# Power_supply.net
KiCad netlist of a schematic drawn in Altium Designer
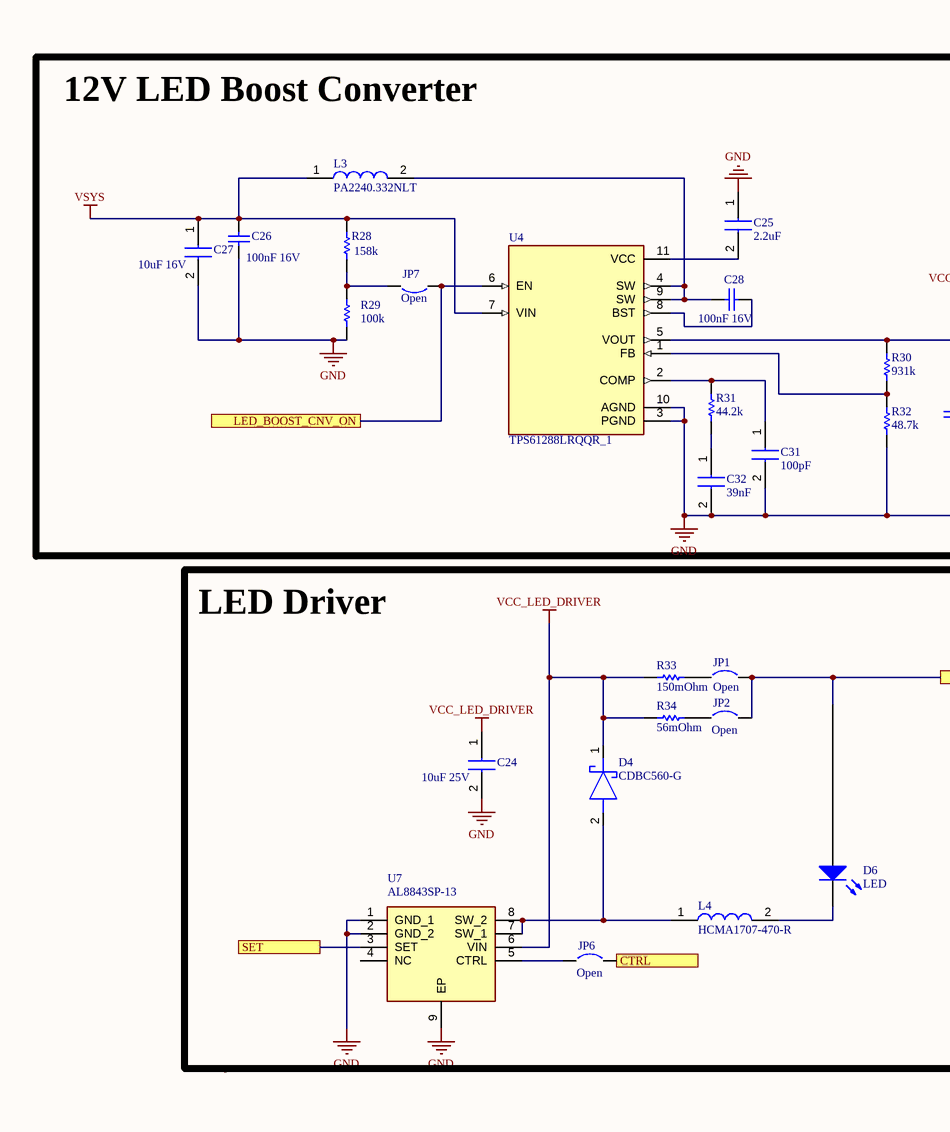
[diagram p0: Power supply.SchDoc, left]
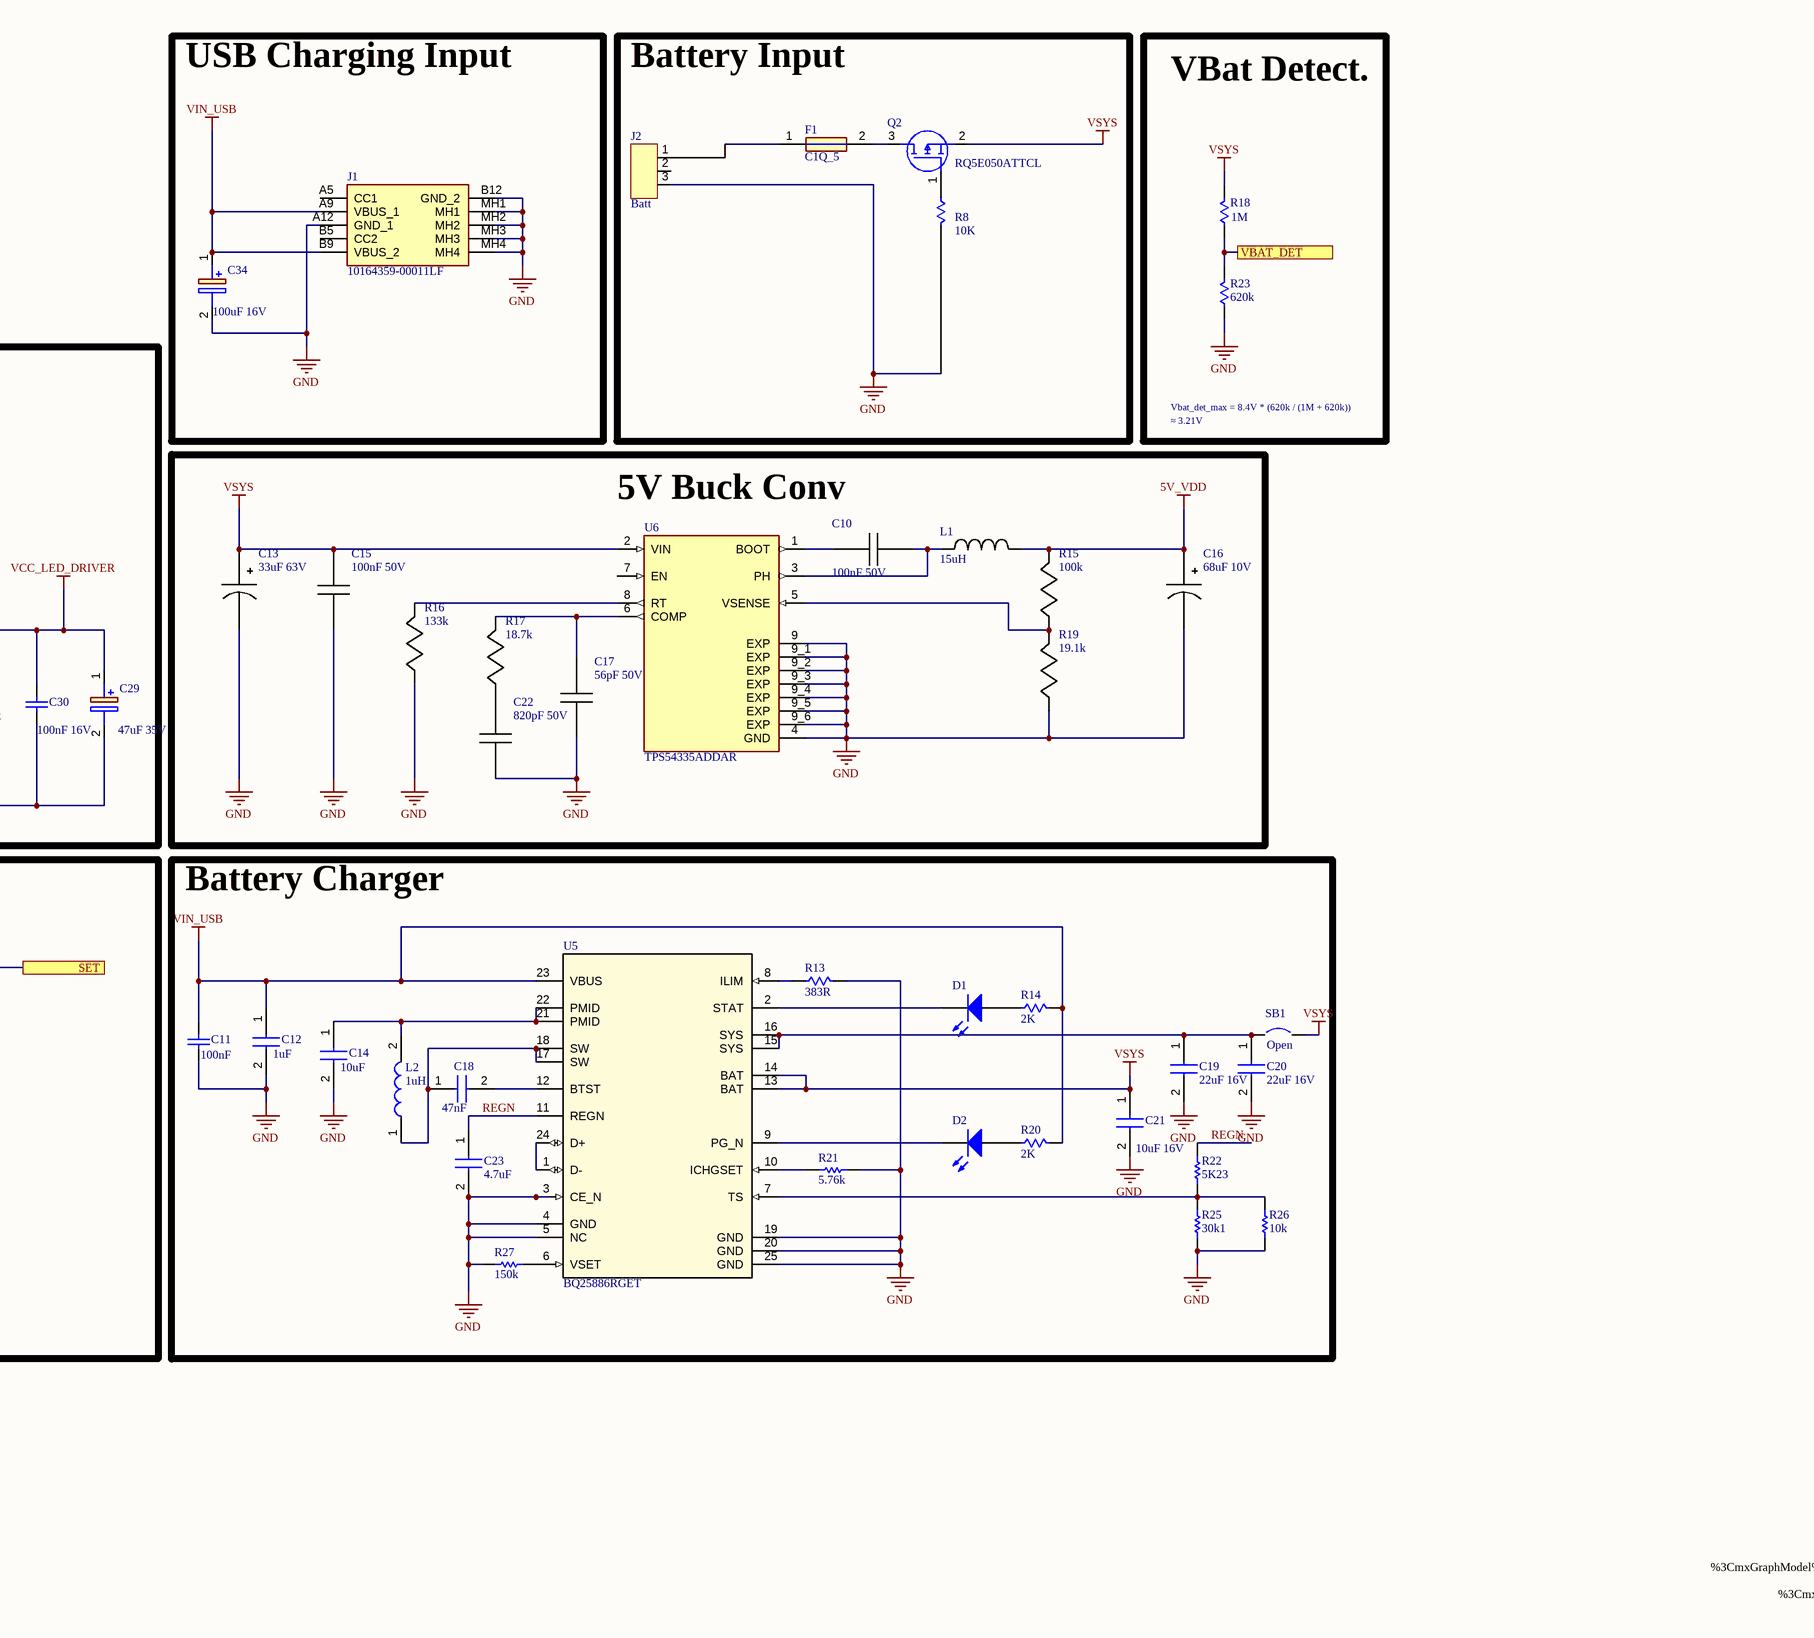
[diagram p1: Power supply.SchDoc, right]

(export (version "E")
  (design (tool "Eeschema 10.0.6"))
  (components
    (comp (ref "C10")
      (value "100nF 50V")
      (footprint "0805C")
      (fields
        (field (name "MANUFACTURER PART NUMBER") "C0805C104M5RACTU")
        (field (name "COPYRIGHT") "Copyright (C) 2018 Accelerated Designs. All rights reserved")
      )
      (libsource (lib "Schlib1") (part "C0805C104M5RACTU"))
    )
    (comp (ref "C11")
      (value "100nF")
      (footprint "C0603")
      (description "CAP CER 0.1UF 16V X7R 0603")
      (fields
        (field (name "MANUFACTURER") "Yageo")
        (field (name "MANUFACTURER PART NUMBER") "CC0603KRX7R7BB104")
      )
      (libsource (lib "Sunbull_V1R0") (part "CC0603KRX7R7BB104"))
    )
    (comp (ref "C12")
      (value "1uF")
      (footprint "PcbLib1:C0805")
      (description "CAP CER 1UF 16V X7R 0805")
      (fields
        (field (name "MOUSER PART NUMBER") "187-CL21B105KOFNNNE")
        (field (name "ARROW PART NUMBER") "CL21B105KOFNNNE")
      )
      (libsource (lib "Sunbull_V1R0") (part "CL21B105KOFNNNE"))
    )
    (comp (ref "C13")
      (value "33uF 63V")
      (footprint "SM_RADIAL_8MM")
      (description "No Description Available")
      (fields
        (field (name "MANUFACTURER PART NUMBER") "EEHZA1J330P")
        (field (name "COPYRIGHT") "Copyright (C) 2018 Accelerated Designs. All rights reserved")
      )
      (libsource (lib "Schlib1") (part "EEHZA1J330P"))
    )
    (comp (ref "C14")
      (value "10uF")
      (footprint "C0603")
      (fields (field (name "MANUFACTURER PART NUMBER") "CL10X106MO8NRNC"))
      (libsource (lib "Sunbull_V1R0") (part "CL21B105KOFNNNE"))
    )
    (comp (ref "C15")
      (value "100nF 50V")
      (footprint "0805C")
      (fields
        (field (name "MANUFACTURER PART NUMBER") "C0805C104M5RACTU")
        (field (name "COPYRIGHT") "Copyright (C) 2018 Accelerated Designs. All rights reserved")
      )
      (libsource (lib "Schlib1") (part "C0805C104M5RACTU"))
    )
    (comp (ref "C16")
      (value "68uF 10V")
      (footprint "SM_RADIAL_5MM")
      (description "10SVPC68M 68uF 10V")
      (fields
        (field (name "MANUFACTURER PART NUMBER") "10SVPC68M")
        (field (name "COPYRIGHT") "Copyright (C) 2018 Accelerated Designs. All rights reserved")
      )
      (libsource (lib "Schlib1") (part "10SVPC68M"))
    )
    (comp (ref "C17")
      (value "56pF 50V")
      (footprint "0805C")
      (fields
        (field (name "MANUFACTURER PART NUMBER") "CC0805JRNPO9BN560")
        (field (name "COPYRIGHT") "Copyright (C) 2018 Accelerated Designs. All rights reserved")
      )
      (libsource (lib "Schlib1") (part "CC0805JRNPO9BN56"))
    )
    (comp (ref "C18")
      (value "47nF")
      (footprint "C0805")
      (fields (field (name "MANUFACTURER PART NUMBER") "KGM21NR71C473KT"))
      (libsource (lib "Sunbull_V1R0") (part "CL21B105KOFNNNE"))
    )
    (comp (ref "C19")
      (value "22uF 16V")
      (footprint "C0603")
      (fields (field (name "MANUFACTURER PART NUMBER") "CL10X106MO8NRNC"))
      (libsource (lib "Sunbull_V1R0") (part "CL21B105KOFNNNE"))
    )
    (comp (ref "C20")
      (value "22uF 16V")
      (footprint "C0603")
      (fields (field (name "MANUFACTURER PART NUMBER") "CL10X106MO8NRNC"))
      (libsource (lib "Sunbull_V1R0") (part "CL21B105KOFNNNE"))
    )
    (comp (ref "C21")
      (value "10uF 16V")
      (footprint "C0603")
      (fields (field (name "MANUFACTURER PART NUMBER") "CL10X106MO8NRNC"))
      (libsource (lib "Sunbull_V1R0") (part "CL21B105KOFNNNE"))
    )
    (comp (ref "C22")
      (value "820pF 50V")
      (footprint "0402")
      (fields
        (field (name "MANUFACTURER PART NUMBER") "CL05C821JB5NNNC")
        (field (name "COPYRIGHT") "Copyright (C) 2018 Accelerated Designs. All rights reserved")
      )
      (libsource (lib "Schlib1") (part "CL05C821JB5NNNC"))
    )
    (comp (ref "C23")
      (value "4.7uF")
      (footprint "C0805")
      (fields (field (name "MANUFACTURER PART NUMBER") "C0805C475M3PAC"))
      (libsource (lib "Sunbull_V1R0") (part "CL21B105KOFNNNE"))
    )
    (comp (ref "C24")
      (value "10uF 25V")
      (footprint "0805C")
      (fields (field (name "MANUFACTURER PART NUMBER") "GRM21BR61E106KA3L"))
      (libsource (lib "Sunbull_V1R0") (part "CL21B105KOFNNNE"))
    )
    (comp (ref "C25")
      (value "2.2uF")
      (footprint "PcbLib1:0805C")
      (fields (field (name "MANUFACTURER PART NUMBER") "CL21B105KOFNNNE"))
      (libsource (lib "Sunbull_V1R0") (part "CL21B105KOFNNNE"))
    )
    (comp (ref "C26")
      (value "100nF 16V")
      (footprint "C0603")
      (description "CAP CER 0.1UF 16V X7R 0603")
      (fields
        (field (name "MANUFACTURER") "Yageo")
        (field (name "MANUFACTURER PART NUMBER") "CC0603KRX7R7BB104")
      )
      (libsource (lib "Sunbull_V1R0") (part "CC0603KRX7R7BB104"))
    )
    (comp (ref "C27")
      (value "10uF 16V")
      (footprint "C0603")
      (fields (field (name "MANUFACTURER PART NUMBER") "CL10X106MO8NRNC"))
      (libsource (lib "Sunbull_V1R0") (part "CL21B105KOFNNNE"))
    )
    (comp (ref "C28")
      (value "100nF 16V")
      (footprint "C0603")
      (description "CAP CER 0.1UF 16V X7R 0603")
      (fields
        (field (name "MANUFACTURER") "Yageo")
        (field (name "MANUFACTURER PART NUMBER") "CC0603KRX7R7BB104")
      )
      (libsource (lib "Sunbull_V1R0") (part "CC0603KRX7R7BB104"))
    )
    (comp (ref "C29")
      (value "47uF 35V")
      (footprint "PcbLib1:CAPAE660X550N")
      (description "Capacitor Polarised")
      (fields
        (field (name "MANUFACTURER PART NUMBER") "865080543009")
        (field (name "MOUSER PART NUMBER") "710-865080543009")
      )
      (libsource (lib "*") (part "865080543009"))
    )
    (comp (ref "C30")
      (value "100nF 16V")
      (footprint "C0603")
      (description "CAP CER 0.1UF 16V X7R 0603")
      (fields
        (field (name "MANUFACTURER") "Yageo")
        (field (name "MANUFACTURER PART NUMBER") "CC0603KRX7R7BB104")
      )
      (libsource (lib "Sunbull_V1R0") (part "CC0603KRX7R7BB104"))
    )
    (comp (ref "C31")
      (value "100pF")
      (footprint "C0603")
      (description "CAP CER 100pF 16V")
      (fields (field (name "MANUFACTURER PART NUMBER") "CC603JRNPO9BN101"))
      (libsource (lib "Sunbull_V1R0") (part "CL21B105KOFNNNE"))
    )
    (comp (ref "C32")
      (value "39nF")
      (footprint "PcbLib1:C0603")
      (description "39nF CAP 0603")
      (fields (field (name "MANUFACTURER PART NUMBER") "06035C393KAT2A"))
      (libsource (lib "Sunbull_V1R0") (part "CL21B105KOFNNNE"))
    )
    (comp (ref "C34")
      (value "100uF 16V")
      (footprint "PcbLib1:CAPAE660X770N")
      (description "Capacitor Polarised")
      (fields
        (field (name "MANUFACTURER PART NUMBER") "865230345005")
        (field (name "MOUSER PART NUMBER") "710-865230345005")
      )
      (libsource (lib "*") (part "865230345005"))
    )
    (comp (ref "D1")
      (value "LED3")
      (footprint "PcbLib1:C0603")
      (description "Typical BLUE SiC LED")
      (fields
        (field (name "MANUFACTURER PART NUMBER") "LTST-C191TBKT")
        (field (name "PUBLISHER") "Altium Limited")
      )
      (libsource (lib "Sunbull_V1R0") (part "LED3"))
    )
    (comp (ref "D2")
      (value "LED3")
      (footprint "PcbLib1:C0603")
      (description "Typical BLUE SiC LED")
      (fields
        (field (name "MANUFACTURER PART NUMBER") "LTST-C191TBKT")
        (field (name "PUBLISHER") "Altium Limited")
      )
      (libsource (lib "Sunbull_V1R0") (part "LED3"))
    )
    (comp (ref "D4")
      (value "CDBC560-G")
      (footprint "PcbLib1:DIOM7959X262N")
      (description "Schottky Diode")
      (fields (field (name "MOUSER PART NUMBER") "750-CDBC560-G"))
      (libsource (lib "*") (part "CDBC560-G"))
    )
    (comp (ref "D6")
      (value "LED")
      (footprint "PcbLib1:SolderWires")
      (libsource (lib "Schlib1") (part "LED3"))
    )
    (comp (ref "F1")
      (value "C1Q_5")
      (footprint "FUSC3216X78N")
      (description "FUSE BOARD MOUNT 5A 125VAC 63VDC")
      (fields (field (name "MOUSER PART NUMBER") "530-C1Q5") (field (name "ARROW PART NUMBER") "C1Q 5"))
      (libsource (lib "Sunbull_V1R0") (part "C1Q_5"))
    )
    (comp (ref "J1")
      (value "10164359-00011LF")
      (footprint "PcbLib1:1016435900011LF")
      (description "Connector")
      (fields (field (name "MOUSER PART NUMBER") "649-10164359-00011LF"))
      (libsource (lib "*") (part "10164359-00011LF"))
    )
    (comp (ref "J2") (value "Batt") (footprint "Batt") (libsource (lib "Schlib1") (part "Batt")))
    (comp (ref "JP1")
      (value "Open")
      (footprint "HDRV2W87P0X254_1X2_768X249X1494P - duplicate")
      (description "Conn\r\n42375-1855\r\n+\r\njumper\r\n60900213621")
      (fields (field (name "PUBLISHER") "Altium Limited"))
      (libsource (lib "Schlib1") (part "Circuit Breaker_close"))
    )
    (comp (ref "JP2")
      (value "Open")
      (footprint "HDRV2W87P0X254_1X2_768X249X1494P - duplicate")
      (description "Conn\r\n42375-1855\r\n+\r\njumper\r\n60900213621")
      (fields (field (name "PUBLISHER") "Altium Limited"))
      (libsource (lib "Schlib1") (part "Circuit Breaker_close"))
    )
    (comp (ref "JP6")
      (value "Open")
      (footprint "HDRV2W87P0X254_1X2_768X249X1494P - duplicate")
      (description "Jumper\r\n42375-1855")
      (fields (field (name "PUBLISHER") "Altium Limited"))
      (libsource (lib "Schlib1") (part "Circuit Breaker_close"))
    )
    (comp (ref "JP7")
      (value "Open")
      (footprint "HDRV2W87P0X254_1X2_768X249X1494P - duplicate")
      (description "Jumper\r\n42375-1855")
      (fields (field (name "PUBLISHER") "Altium Limited"))
      (libsource (lib "Schlib1") (part "Circuit Breaker_close"))
    )
    (comp (ref "L1")
      (value "15uH")
      (footprint "SRR1280")
      (description "No Description Available")
      (fields
        (field (name "MANUFACTURER PART NUMBER") "SRR1280-150M")
        (field (name "COPYRIGHT") "Copyright (C) 2018 Accelerated Designs. All rights reserved")
      )
      (libsource (lib "Schlib1") (part "SRR1280-150M"))
    )
    (comp (ref "L2")
      (value "1uH")
      (footprint "PcbLib1:VLS5045EX330M")
      (description "Inductor")
      (fields
        (field (name "MANUFACTURER PART NUMBER") "VLS5045EX-1R0N")
        (field (name "MOUSER PART NUMBER") "810-VLS5045EX-1R0N")
      )
      (libsource (lib "Schlib1") (part "VLS5045EX-1R0N"))
    )
    (comp (ref "L3")
      (value "PA2240.332NLT")
      (footprint "PA2240332NLT")
      (description "Inductor")
      (fields (field (name "MOUSER PART NUMBER") "673-PA2240.332NLT"))
      (libsource (lib "Schlib1") (part "PA2240.332NLT"))
    )
    (comp (ref "L4")
      (value "HCMA1707-470-R")
      (footprint "PcbLib1:INDPM172168X700N")
      (description "Inductor")
      (fields (field (name "MOUSER PART NUMBER") "704-HCMA1707-470-R"))
      (libsource (lib "Schlib1") (part "HCMA1707-470-R"))
    )
    (comp (ref "Q2")
      (value "RQ5E050ATTCL")
      (footprint "SOT95P280X100-3N")
      (description "MOSFET P-CH 30V 5A TSMT3")
      (fields (field (name "MOUSER PART NUMBER") "755-RQ5E050ATTCL") (field (name "MANUFACTURER") "Rohm"))
      (libsource (lib "Sunbull_V1R0") (part "RQ5E050ATTCL"))
    )
    (comp (ref "R8")
      (value "10K")
      (footprint "PcbLib1:0603")
      (description "RES SMD 10K OHM 1% 1/10W 0603")
      (fields (field (name "TOLERANCE") "1%") (field (name "MANUFACTURER PART NUMBER") "RC0603FR-0710KL"))
      (libsource (lib "Sunbull_V1R0") (part "RC0603FR-0710KL"))
    )
    (comp (ref "R13")
      (value "383R")
      (footprint "R0603")
      (fields
        (field (name "MANUFACTURER PART NUMBER") "ERJ-3EKF3830V")
        (field (name "TOLERANCE") "±1%")
        (field (name "MOUSER PART NUMBER") "603-RC0603FR-072KL")
      )
      (libsource (lib "Sunbull_V1R0") (part "RC0603FR-072KL"))
    )
    (comp (ref "R14")
      (value "2K")
      (footprint "PcbLib1:R0603")
      (description "RES SMD 2K OHM 1% 1/10W 0603")
      (fields
        (field (name "MANUFACTURER") "Yageo")
        (field (name "MANUFACTURER PART NUMBER") "RC0603FR-072KL")
      )
      (libsource (lib "Sunbull_V1R0") (part "RC0603FR-072KL"))
    )
    (comp (ref "R15")
      (value "100k")
      (footprint "0402")
      (description "100k Resistor")
      (fields
        (field (name "POWER") "0.063")
        (field (name "TOLERANCE") "1.0")
        (field (name "COPYRIGHT") "Copyright (C) 2018 Accelerated Designs. All rights reserved")
      )
      (libsource (lib "Schlib1") (part "CRCW0402100KFKED"))
    )
    (comp (ref "R16")
      (value "133k")
      (footprint "0201")
      (fields
        (field (name "POWER") "0.05")
        (field (name "TOLERANCE") "1.0")
        (field (name "MANUFACTURER PART NUMBER") "RC0201FR-07133KL")
        (field (name "COPYRIGHT") "Copyright (C) 2018 Accelerated Designs. All rights reserved")
      )
      (libsource (lib "Schlib1") (part "RC0201FR-07133KL"))
    )
    (comp (ref "R17")
      (value "18.7k")
      (footprint "0201")
      (fields
        (field (name "POWER") "0.05")
        (field (name "TOLERANCE") "1.0")
        (field (name "MANUFACTURER PART NUMBER") "RC0201FR-0718K7L")
        (field (name "COPYRIGHT") "Copyright (C) 2018 Accelerated Designs. All rights reserved")
      )
      (libsource (lib "Schlib1") (part "RC0201FR-0718K7L"))
    )
    (comp (ref "R18")
      (value "1M")
      (footprint "PcbLib1:0603")
      (description "RES SMD 1M OHM 1% 1/10W 0603")
      (fields (field (name "MANUFACTURER PART NUMBER") "RC0603FR-071ML") (field (name "TOLERANCE") "1%"))
      (libsource (lib "Sunbull_V1R0") (part "RC0603FR-071ML"))
    )
    (comp (ref "R19")
      (value "19.1k")
      (footprint "0402")
      (fields
        (field (name "POWER") "0.063")
        (field (name "TOLERANCE") "1.0")
        (field (name "MANUFACTURER PART NUMBER") "CRCW040219K1FKED")
        (field (name "COPYRIGHT") "Copyright (C) 2018 Accelerated Designs. All rights reserved")
      )
      (libsource (lib "Schlib1") (part "CRCW040219K1FKED"))
    )
    (comp (ref "R20")
      (value "2K")
      (footprint "PcbLib1:R0603")
      (description "RES SMD 2K OHM 1% 1/10W 0603")
      (fields
        (field (name "MANUFACTURER") "Yageo")
        (field (name "MANUFACTURER PART NUMBER") "RC0603FR-072KL")
      )
      (libsource (lib "Sunbull_V1R0") (part "RC0603FR-072KL"))
    )
    (comp (ref "R21")
      (value "5.76k")
      (footprint "R0603")
      (description "Resistor DNP 0603 5.76k")
      (fields (field (name "MANUFACTURER PART NUMBER") "RC0603FR-075K76L"))
      (libsource (lib "Sunbull_V1R0") (part "RES_DNP"))
    )
    (comp (ref "R22")
      (value "5K23")
      (footprint "R0603")
      (description "Resistor DNP 0603")
      (fields (field (name "MANUFACTURER PART NUMBER") "ERJ-3EKF5231V"))
      (libsource (lib "Sunbull_V1R0") (part "RES_DNP"))
    )
    (comp (ref "R23")
      (value "620k")
      (footprint "PcbLib1:0603")
      (description "RES SMD 620k OHM 1% 1/10W 0603")
      (fields (field (name "MANUFACTURER PART NUMBER") "CRCW0603620KFKEA") (field (name "TOLERANCE") "1%"))
      (libsource (lib "Sunbull_V1R0") (part "RC0603FR-071ML"))
    )
    (comp (ref "R25")
      (value "30k1")
      (footprint "PcbLib1:R0603")
      (description "Resistor DNP 0603")
      (fields (field (name "MANUFACTURER PART NUMBER") "CRCW0603-30.1K-E3"))
      (libsource (lib "Sunbull_V1R0") (part "RES_DNP"))
    )
    (comp (ref "R26")
      (value "10k")
      (footprint "PcbLib1:R0603")
      (description "Resistor DNP 0603")
      (fields (field (name "MANUFACTURER PART NUMBER") "CRCW0603-10K-E3"))
      (libsource (lib "Sunbull_V1R0") (part "RES_DNP"))
    )
    (comp (ref "R27")
      (value "150k")
      (footprint "R0603")
      (description "Resistor DNP 0603")
      (fields (field (name "MANUFACTURER PART NUMBER") "RT0603BRE07250RL"))
      (libsource (lib "Sunbull_V1R0") (part "RES_DNP"))
    )
    (comp (ref "R28")
      (value "158k")
      (footprint "PcbLib1:0603")
      (description "Resistor DNP 0603 158k")
      (fields (field (name "MANUFACTURER PART NUMBER") "CRCW0603-158K-E3"))
      (libsource (lib "Sunbull_V1R0") (part "RES_DNP"))
    )
    (comp (ref "R29")
      (value "100k")
      (footprint "R0603")
      (description "RES SMD 100K OHM 1% 1/10W 0603")
      (fields
        (field (name "MANUFACTURER") "Yageo")
        (field (name "MANUFACTURER PART NUMBER") "RC0603FR-07100KL")
      )
      (libsource (lib "Sunbull_V1R0") (part "RC0603FR-07100KL"))
    )
    (comp (ref "R30")
      (value "931k")
      (footprint "PcbLib1:R0603")
      (description "Resistor DNP 0603")
      (fields (field (name "MANUFACTURER PART NUMBER") "CRCW0603-931K-E3"))
      (libsource (lib "Sunbull_V1R0") (part "RES_DNP"))
    )
    (comp (ref "R31")
      (value "44.2k")
      (footprint "PcbLib1:R0603")
      (description "Resistor DNP 0603")
      (fields (field (name "MANUFACTURER PART NUMBER") "CRCW0603-44.2K-E3"))
      (libsource (lib "Sunbull_V1R0") (part "RES_DNP"))
    )
    (comp (ref "R32")
      (value "48.7k")
      (footprint "PcbLib1:R0603")
      (description "Resistor DNP 0603")
      (fields (field (name "MANUFACTURER PART NUMBER") "CRCW0603-48.7K-E3"))
      (libsource (lib "Sunbull_V1R0") (part "RES_DNP"))
    )
    (comp (ref "R33")
      (value "150mOhm")
      (footprint "PcbLib1:R0603")
      (description "Resistor DNP 0603 150mOhm RL0603FR-070R15L")
      (fields (field (name "MANUFACTURER PART NUMBER") "RL0603FR-070R15L"))
      (libsource (lib "Sunbull_V1R0") (part "RES_DNP"))
    )
    (comp (ref "R34")
      (value "56mOhm")
      (footprint "PcbLib1:R0603")
      (description "Resistor DNP 0603 ERJ-3BWFR056V 56mOhm")
      (fields (field (name "MANUFACTURER PART NUMBER") "ERJ-3BWFR056V"))
      (libsource (lib "Sunbull_V1R0") (part "RES_DNP"))
    )
    (comp (ref "SB1")
      (value "Open")
      (footprint "SB_0603")
      (description "Circuit Breaker")
      (fields (field (name "PUBLISHER") "Altium Limited"))
      (libsource (lib "Sunbull_V1R0") (part "Circuit Breaker_close"))
    )
    (comp (ref "U4")
      (value "TPS61288LRQQR_1")
      (footprint "CONV_TPS61288LRQQR")
      (description "18-V, 15-A synchronous boost converter")
      (fields
        (field (name "MF") "Texas Instruments")
        (field (name "MANUFACTURER PART NUMBER") "TPS61288LRQQR")
      )
      (libsource (lib "Schlib1") (part "TPS61288LRQQR_1"))
    )
    (comp (ref "U5")
      (value "BQ25886RGET")
      (footprint "RGE0024H")
      (description "No Description Available")
      (libsource (lib "Schlib1") (part "BQ25886RGET"))
    )
    (comp (ref "U6")
      (value "TPS54335ADDAR")
      (footprint "IC_TPS54335ADDAR")
      (description "4.5V to 28V Input, 3A, Synchronous, Step-Down Converter with Eco-mode")
      (libsource (lib "Schlib1") (part "TPS54335ADDAR"))
    )
    (comp (ref "U7")
      (value "AL8843SP-13")
      (footprint "PcbLib1:SOIC127P600X163-9N")
      (description "Integrated Circuit")
      (fields (field (name "MOUSER PART NUMBER") "621-AL8843SP-13"))
      (libsource (lib "Schlib1") (part "AL8843SP-13"))
    )
  )
  (nets
    (net (code "1") (name "/CTRL") (class "Default")
      (node (ref "JP6") (pin "2") (pinfunction "2_2") (pintype "passive"))
    )
    (net (code "2") (name "/LED_BOOST_CNV_ON") (class "Default")
      (node (ref "JP7") (pin "1") (pinfunction "1_1") (pintype "passive"))
      (node (ref "U4") (pin "6") (pinfunction "EN_6") (pintype "input"))
    )
    (net (code "3") (name "/REGN") (class "Default")
      (node (ref "C23") (pin "1") (pinfunction "1_1") (pintype "passive"))
      (node (ref "R22") (pin "1") (pinfunction "1_1") (pintype "passive"))
      (node (ref "U5") (pin "11") (pinfunction "REGN_11") (pintype "power_in"))
    )
    (net (code "4") (name "/SET") (class "Default")
      (node (ref "D6") (pin "1") (pinfunction "A_1") (pintype "passive"))
      (node (ref "JP1") (pin "2") (pinfunction "2_2") (pintype "passive"))
      (node (ref "JP2") (pin "2") (pinfunction "2_2") (pintype "passive"))
      (node (ref "U7") (pin "3") (pinfunction "SET_3") (pintype "passive"))
    )
    (net (code "5") (name "/VBAT_DET") (class "Default")
      (node (ref "R18") (pin "1") (pinfunction "1_1") (pintype "passive"))
      (node (ref "R23") (pin "2") (pinfunction "2_2") (pintype "passive"))
    )
    (net (code "6") (name "5V_VDD") (class "Default")
      (node (ref "C16") (pin "1") (pinfunction "+_1") (pintype "passive"))
      (node (ref "L1") (pin "2") (pinfunction "2_2") (pintype "passive"))
      (node (ref "R15") (pin "1") (pinfunction "1_1") (pintype "passive"))
    )
    (net (code "7") (name "GND") (class "Default")
      (node (ref "C11") (pin "1") (pinfunction "1_1") (pintype "passive"))
      (node (ref "C12") (pin "2") (pinfunction "2_2") (pintype "passive"))
      (node (ref "C13") (pin "2") (pinfunction "-_2") (pintype "passive"))
      (node (ref "C14") (pin "2") (pinfunction "2_2") (pintype "passive"))
      (node (ref "C15") (pin "1") (pinfunction "1_1") (pintype "passive"))
      (node (ref "C16") (pin "2") (pinfunction "-_2") (pintype "passive"))
      (node (ref "C17") (pin "2") (pinfunction "2_2") (pintype "passive"))
      (node (ref "C19") (pin "2") (pinfunction "2_2") (pintype "passive"))
      (node (ref "C20") (pin "2") (pinfunction "2_2") (pintype "passive"))
      (node (ref "C21") (pin "2") (pinfunction "2_2") (pintype "passive"))
      (node (ref "C22") (pin "2") (pinfunction "2_2") (pintype "passive"))
      (node (ref "C23") (pin "2") (pinfunction "2_2") (pintype "passive"))
      (node (ref "C24") (pin "2") (pinfunction "2_2") (pintype "passive"))
      (node (ref "C25") (pin "1") (pinfunction "1_1") (pintype "passive"))
      (node (ref "C26") (pin "1") (pinfunction "1_1") (pintype "passive"))
      (node (ref "C27") (pin "2") (pinfunction "2_2") (pintype "passive"))
      (node (ref "C29") (pin "2") (pinfunction "-_2") (pintype "passive"))
      (node (ref "C30") (pin "1") (pinfunction "1_1") (pintype "passive"))
      (node (ref "C31") (pin "2") (pinfunction "2_2") (pintype "passive"))
      (node (ref "C32") (pin "2") (pinfunction "2_2") (pintype "passive"))
      (node (ref "C34") (pin "2") (pinfunction "-_2") (pintype "passive"))
      (node (ref "J1") (pin "A12") (pinfunction "GND_1_A12") (pintype "passive"))
      (node (ref "J1") (pin "B12") (pinfunction "GND_2_B12") (pintype "passive"))
      (node (ref "J1") (pin "MH1") (pinfunction "MH1_MH1") (pintype "passive"))
      (node (ref "J1") (pin "MH2") (pinfunction "MH2_MH2") (pintype "passive"))
      (node (ref "J1") (pin "MH3") (pinfunction "MH3_MH3") (pintype "passive"))
      (node (ref "J1") (pin "MH4") (pinfunction "MH4_MH4") (pintype "passive"))
      (node (ref "J2") (pin "3") (pinfunction "3_3") (pintype "passive"))
      (node (ref "R13") (pin "2") (pinfunction "2_2") (pintype "passive"))
      (node (ref "R16") (pin "2") (pinfunction "2_2") (pintype "passive"))
      (node (ref "R19") (pin "2") (pinfunction "2_2") (pintype "passive"))
      (node (ref "R21") (pin "2") (pinfunction "2_2") (pintype "passive"))
      (node (ref "R23") (pin "1") (pinfunction "1_1") (pintype "passive"))
      (node (ref "R25") (pin "2") (pinfunction "2_2") (pintype "passive"))
      (node (ref "R26") (pin "2") (pinfunction "2_2") (pintype "passive"))
      (node (ref "R27") (pin "1") (pinfunction "1_1") (pintype "passive"))
      (node (ref "R29") (pin "1") (pinfunction "1_1") (pintype "passive"))
      (node (ref "R32") (pin "1") (pinfunction "1_1") (pintype "passive"))
      (node (ref "R8") (pin "2") (pinfunction "2_2") (pintype "passive"))
      (node (ref "U4") (pin "10") (pinfunction "AGND_10") (pintype "power_in"))
      (node (ref "U4") (pin "3") (pinfunction "PGND_3") (pintype "power_in"))
      (node (ref "U5") (pin "19") (pinfunction "GND_19") (pintype "power_in"))
      (node (ref "U5") (pin "20") (pinfunction "GND_20") (pintype "power_in"))
      (node (ref "U5") (pin "25") (pinfunction "GND_25") (pintype "power_in"))
      (node (ref "U5") (pin "3") (pinfunction "CE_N_3") (pintype "input"))
      (node (ref "U5") (pin "4") (pinfunction "GND_4") (pintype "power_in"))
      (node (ref "U5") (pin "5") (pinfunction "NC_5") (pintype "passive"))
      (node (ref "U6") (pin "4") (pinfunction "GND_4") (pintype "power_in"))
      (node (ref "U6") (pin "9") (pinfunction "EXP_9") (pintype "power_in"))
      (node (ref "U6") (pin "9_1") (pinfunction "EXP_9_1") (pintype "power_in"))
      (node (ref "U6") (pin "9_2") (pinfunction "EXP_9_2") (pintype "power_in"))
      (node (ref "U6") (pin "9_3") (pinfunction "EXP_9_3") (pintype "power_in"))
      (node (ref "U6") (pin "9_4") (pinfunction "EXP_9_4") (pintype "power_in"))
      (node (ref "U6") (pin "9_5") (pinfunction "EXP_9_5") (pintype "power_in"))
      (node (ref "U6") (pin "9_6") (pinfunction "EXP_9_6") (pintype "power_in"))
      (node (ref "U7") (pin "1") (pinfunction "GND_1_1") (pintype "passive"))
      (node (ref "U7") (pin "2") (pinfunction "GND_2_2") (pintype "passive"))
      (node (ref "U7") (pin "9") (pinfunction "EP_9") (pintype "passive"))
    )
    (net (code "8") (name "Net-(C14-Pad1)") (class "Default")
      (node (ref "C14") (pin "1") (pinfunction "1_1") (pintype "passive"))
      (node (ref "L2") (pin "2") (pinfunction "2_2") (pintype "passive"))
      (node (ref "U5") (pin "21") (pinfunction "PMID_21") (pintype "power_in"))
      (node (ref "U5") (pin "22") (pinfunction "PMID_22") (pintype "power_in"))
    )
    (net (code "9") (name "Net-(C18-Pad1)") (class "Default")
      (node (ref "C18") (pin "1") (pinfunction "1_1") (pintype "passive"))
      (node (ref "L2") (pin "1") (pinfunction "1_1") (pintype "passive"))
      (node (ref "U5") (pin "17") (pinfunction "SW_17") (pintype "power_in"))
      (node (ref "U5") (pin "18") (pinfunction "SW_18") (pintype "power_in"))
    )
    (net (code "10") (name "Net-(C19-Pad1)") (class "Default")
      (node (ref "C19") (pin "1") (pinfunction "1_1") (pintype "passive"))
      (node (ref "C20") (pin "1") (pinfunction "1_1") (pintype "passive"))
      (node (ref "SB1") (pin "1") (pinfunction "1_1") (pintype "passive"))
      (node (ref "U5") (pin "15") (pinfunction "SYS_15") (pintype "power_in"))
      (node (ref "U5") (pin "16") (pinfunction "SYS_16") (pintype "power_in"))
    )
    (net (code "11") (name "Net-(C22-Pad1)") (class "Default")
      (node (ref "C22") (pin "1") (pinfunction "1_1") (pintype "passive"))
      (node (ref "R17") (pin "2") (pinfunction "2_2") (pintype "passive"))
    )
    (net (code "12") (name "Net-(C28-Pad2)") (class "Default")
      (node (ref "C28") (pin "2") (pinfunction "2_2") (pintype "passive"))
      (node (ref "L3") (pin "2") (pinfunction "2_2") (pintype "passive"))
      (node (ref "U4") (pin "4") (pinfunction "SW_4") (pintype "output"))
      (node (ref "U4") (pin "9") (pinfunction "SW_9") (pintype "output"))
    )
    (net (code "13") (name "Net-(C32-Pad1)") (class "Default")
      (node (ref "C32") (pin "1") (pinfunction "1_1") (pintype "passive"))
      (node (ref "R31") (pin "1") (pinfunction "1_1") (pintype "passive"))
    )
    (net (code "14") (name "Net-(D1-A)") (class "Default")
      (node (ref "D1") (pin "1") (pinfunction "A_1") (pintype "passive"))
      (node (ref "R14") (pin "1") (pinfunction "1_1") (pintype "passive"))
    )
    (net (code "15") (name "Net-(D1-K)") (class "Default")
      (node (ref "D1") (pin "2") (pinfunction "K_2") (pintype "passive"))
      (node (ref "U5") (pin "2") (pinfunction "STAT_2") (pintype "open_collector"))
    )
    (net (code "16") (name "Net-(D2-A)") (class "Default")
      (node (ref "D2") (pin "1") (pinfunction "A_1") (pintype "passive"))
      (node (ref "R20") (pin "1") (pinfunction "1_1") (pintype "passive"))
    )
    (net (code "17") (name "Net-(D2-K)") (class "Default")
      (node (ref "D2") (pin "2") (pinfunction "K_2") (pintype "passive"))
      (node (ref "U5") (pin "9") (pinfunction "PG_N_9") (pintype "open_collector"))
    )
    (net (code "18") (name "Net-(D4-A)") (class "Default")
      (node (ref "D4") (pin "2") (pinfunction "A_2") (pintype "passive"))
      (node (ref "L4") (pin "1") (pinfunction "1_1") (pintype "passive"))
      (node (ref "U7") (pin "7") (pinfunction "SW_1_7") (pintype "passive"))
      (node (ref "U7") (pin "8") (pinfunction "SW_2_8") (pintype "passive"))
    )
    (net (code "19") (name "Net-(D6-K)") (class "Default")
      (node (ref "D6") (pin "2") (pinfunction "K_2") (pintype "passive"))
      (node (ref "L4") (pin "2") (pinfunction "2_2") (pintype "passive"))
    )
    (net (code "20") (name "Net-(F1-Pad1)") (class "Default")
      (node (ref "F1") (pin "1") (pinfunction "1_1") (pintype "passive"))
      (node (ref "J2") (pin "1") (pinfunction "1_1") (pintype "passive"))
    )
    (net (code "21") (name "Net-(JP1-Pad1)") (class "Default")
      (node (ref "JP1") (pin "1") (pinfunction "1_1") (pintype "passive"))
      (node (ref "R33") (pin "1") (pinfunction "1_1") (pintype "passive"))
    )
    (net (code "22") (name "Net-(JP2-Pad1)") (class "Default")
      (node (ref "JP2") (pin "1") (pinfunction "1_1") (pintype "passive"))
      (node (ref "R34") (pin "1") (pinfunction "1_1") (pintype "passive"))
    )
    (net (code "23") (name "Net-(JP7-Pad2)") (class "Default")
      (node (ref "JP7") (pin "2") (pinfunction "2_2") (pintype "passive"))
      (node (ref "R28") (pin "1") (pinfunction "1_1") (pintype "passive"))
      (node (ref "R29") (pin "2") (pinfunction "2_2") (pintype "passive"))
    )
    (net (code "24") (name "Net-(Q2-D)") (class "Default")
      (node (ref "F1") (pin "2") (pinfunction "2_2") (pintype "passive"))
      (node (ref "Q2") (pin "3") (pinfunction "D_3") (pintype "power_in"))
    )
    (net (code "25") (name "Net-(Q2-G)") (class "Default")
      (node (ref "Q2") (pin "1") (pinfunction "G_1") (pintype "power_in"))
      (node (ref "R8") (pin "1") (pinfunction "1_1") (pintype "passive"))
    )
    (net (code "26") (name "Net-(U4-BST)") (class "Default")
      (node (ref "C28") (pin "1") (pinfunction "1_1") (pintype "passive"))
      (node (ref "U4") (pin "8") (pinfunction "BST_8") (pintype "output"))
    )
    (net (code "27") (name "Net-(U4-COMP)") (class "Default")
      (node (ref "C31") (pin "1") (pinfunction "1_1") (pintype "passive"))
      (node (ref "R31") (pin "2") (pinfunction "2_2") (pintype "passive"))
      (node (ref "U4") (pin "2") (pinfunction "COMP_2") (pintype "output"))
    )
    (net (code "28") (name "Net-(U4-FB)") (class "Default")
      (node (ref "R30") (pin "1") (pinfunction "1_1") (pintype "passive"))
      (node (ref "R32") (pin "2") (pinfunction "2_2") (pintype "passive"))
      (node (ref "U4") (pin "1") (pinfunction "FB_1") (pintype "input"))
    )
    (net (code "29") (name "Net-(U4-VCC)") (class "Default")
      (node (ref "C25") (pin "2") (pinfunction "2_2") (pintype "passive"))
      (node (ref "U4") (pin "11") (pinfunction "VCC_11") (pintype "power_in"))
    )
    (net (code "30") (name "Net-(U5-BTST)") (class "Default")
      (node (ref "C18") (pin "2") (pinfunction "2_2") (pintype "passive"))
      (node (ref "U5") (pin "12") (pinfunction "BTST_12") (pintype "power_in"))
    )
    (net (code "31") (name "Net-(U5-D+)") (class "Default")
      (node (ref "U5") (pin "1") (pinfunction "D-_1") (pintype "bidirectional"))
      (node (ref "U5") (pin "24") (pinfunction "D+_24") (pintype "bidirectional"))
    )
    (net (code "32") (name "Net-(U5-ICHGSET)") (class "Default")
      (node (ref "R21") (pin "1") (pinfunction "1_1") (pintype "passive"))
      (node (ref "U5") (pin "10") (pinfunction "ICHGSET_10") (pintype "input"))
    )
    (net (code "33") (name "Net-(U5-ILIM)") (class "Default")
      (node (ref "R13") (pin "1") (pinfunction "1_1") (pintype "passive"))
      (node (ref "U5") (pin "8") (pinfunction "ILIM_8") (pintype "input"))
    )
    (net (code "34") (name "Net-(U5-TS)") (class "Default")
      (node (ref "R22") (pin "2") (pinfunction "2_2") (pintype "passive"))
      (node (ref "R25") (pin "1") (pinfunction "1_1") (pintype "passive"))
      (node (ref "R26") (pin "1") (pinfunction "1_1") (pintype "passive"))
      (node (ref "U5") (pin "7") (pinfunction "TS_7") (pintype "input"))
    )
    (net (code "35") (name "Net-(U5-VSET)") (class "Default")
      (node (ref "R27") (pin "2") (pinfunction "2_2") (pintype "passive"))
      (node (ref "U5") (pin "6") (pinfunction "VSET_6") (pintype "input"))
    )
    (net (code "36") (name "Net-(U6-BOOT)") (class "Default")
      (node (ref "C10") (pin "1") (pinfunction "1_1") (pintype "passive"))
      (node (ref "U6") (pin "1") (pinfunction "BOOT_1") (pintype "output"))
    )
    (net (code "37") (name "Net-(U6-COMP)") (class "Default")
      (node (ref "C17") (pin "1") (pinfunction "1_1") (pintype "passive"))
      (node (ref "R17") (pin "1") (pinfunction "1_1") (pintype "passive"))
      (node (ref "U6") (pin "6") (pinfunction "COMP_6") (pintype "output"))
    )
    (net (code "38") (name "Net-(U6-PH)") (class "Default")
      (node (ref "C10") (pin "2") (pinfunction "2_2") (pintype "passive"))
      (node (ref "L1") (pin "1") (pinfunction "1_1") (pintype "passive"))
      (node (ref "U6") (pin "3") (pinfunction "PH_3") (pintype "output"))
    )
    (net (code "39") (name "Net-(U6-RT)") (class "Default")
      (node (ref "R16") (pin "1") (pinfunction "1_1") (pintype "passive"))
      (node (ref "U6") (pin "8") (pinfunction "RT_8") (pintype "output"))
    )
    (net (code "40") (name "Net-(U6-VSENSE)") (class "Default")
      (node (ref "R15") (pin "2") (pinfunction "2_2") (pintype "passive"))
      (node (ref "R19") (pin "1") (pinfunction "1_1") (pintype "passive"))
      (node (ref "U6") (pin "5") (pinfunction "VSENSE_5") (pintype "input"))
    )
    (net (code "41") (name "Net-(U7-CTRL)") (class "Default")
      (node (ref "JP6") (pin "1") (pinfunction "1_1") (pintype "passive"))
      (node (ref "U7") (pin "5") (pinfunction "CTRL_5") (pintype "passive"))
    )
    (net (code "42") (name "VCC_LED_DRIVER") (class "Default")
      (node (ref "C24") (pin "1") (pinfunction "1_1") (pintype "passive"))
      (node (ref "C29") (pin "1") (pinfunction "+_1") (pintype "passive"))
      (node (ref "C30") (pin "2") (pinfunction "2_2") (pintype "passive"))
      (node (ref "D4") (pin "1") (pinfunction "K_1") (pintype "passive"))
      (node (ref "R30") (pin "2") (pinfunction "2_2") (pintype "passive"))
      (node (ref "R33") (pin "2") (pinfunction "2_2") (pintype "passive"))
      (node (ref "R34") (pin "2") (pinfunction "2_2") (pintype "passive"))
      (node (ref "U4") (pin "5") (pinfunction "VOUT_5") (pintype "output"))
      (node (ref "U7") (pin "6") (pinfunction "VIN_6") (pintype "passive"))
    )
    (net (code "43") (name "VIN_USB") (class "Default")
      (node (ref "C11") (pin "2") (pinfunction "2_2") (pintype "passive"))
      (node (ref "C12") (pin "1") (pinfunction "1_1") (pintype "passive"))
      (node (ref "C34") (pin "1") (pinfunction "+_1") (pintype "passive"))
      (node (ref "J1") (pin "A9") (pinfunction "VBUS_1_A9") (pintype "passive"))
      (node (ref "J1") (pin "B9") (pinfunction "VBUS_2_B9") (pintype "passive"))
      (node (ref "R14") (pin "2") (pinfunction "2_2") (pintype "passive"))
      (node (ref "R20") (pin "2") (pinfunction "2_2") (pintype "passive"))
      (node (ref "U5") (pin "23") (pinfunction "VBUS_23") (pintype "power_in"))
    )
    (net (code "44") (name "VSYS") (class "Default")
      (node (ref "C13") (pin "1") (pinfunction "+_1") (pintype "passive"))
      (node (ref "C15") (pin "2") (pinfunction "2_2") (pintype "passive"))
      (node (ref "C21") (pin "1") (pinfunction "1_1") (pintype "passive"))
      (node (ref "C26") (pin "2") (pinfunction "2_2") (pintype "passive"))
      (node (ref "C27") (pin "1") (pinfunction "1_1") (pintype "passive"))
      (node (ref "L3") (pin "1") (pinfunction "1_1") (pintype "passive"))
      (node (ref "Q2") (pin "2") (pinfunction "S_2") (pintype "power_in"))
      (node (ref "R18") (pin "2") (pinfunction "2_2") (pintype "passive"))
      (node (ref "R28") (pin "2") (pinfunction "2_2") (pintype "passive"))
      (node (ref "SB1") (pin "2") (pinfunction "2_2") (pintype "passive"))
      (node (ref "U4") (pin "7") (pinfunction "VIN_7") (pintype "input"))
      (node (ref "U5") (pin "13") (pinfunction "BAT_13") (pintype "power_in"))
      (node (ref "U5") (pin "14") (pinfunction "BAT_14") (pintype "power_in"))
      (node (ref "U6") (pin "2") (pinfunction "VIN_2") (pintype "input"))
    )
    (net (code "45") (name "unconnected-(J1-CC1-PadA5)") (class "Default")
      (node (ref "J1") (pin "A5") (pinfunction "CC1_A5") (pintype "passive"))
    )
    (net (code "46") (name "unconnected-(J1-CC2-PadB5)") (class "Default")
      (node (ref "J1") (pin "B5") (pinfunction "CC2_B5") (pintype "passive"))
    )
    (net (code "47") (name "unconnected-(J2-Pad2)") (class "Default")
      (node (ref "J2") (pin "2") (pinfunction "2_2") (pintype "passive"))
    )
    (net (code "48") (name "unconnected-(U6-EN-Pad7)") (class "Default")
      (node (ref "U6") (pin "7") (pinfunction "EN_7") (pintype "input"))
    )
    (net (code "49") (name "unconnected-(U7-NC-Pad4)") (class "Default")
      (node (ref "U7") (pin "4") (pinfunction "NC_4") (pintype "passive"))
    )
  )
)
